# Adafruit_PA1010D_Mini_GPS.net
KiCad netlist of a schematic drawn in EAGLE
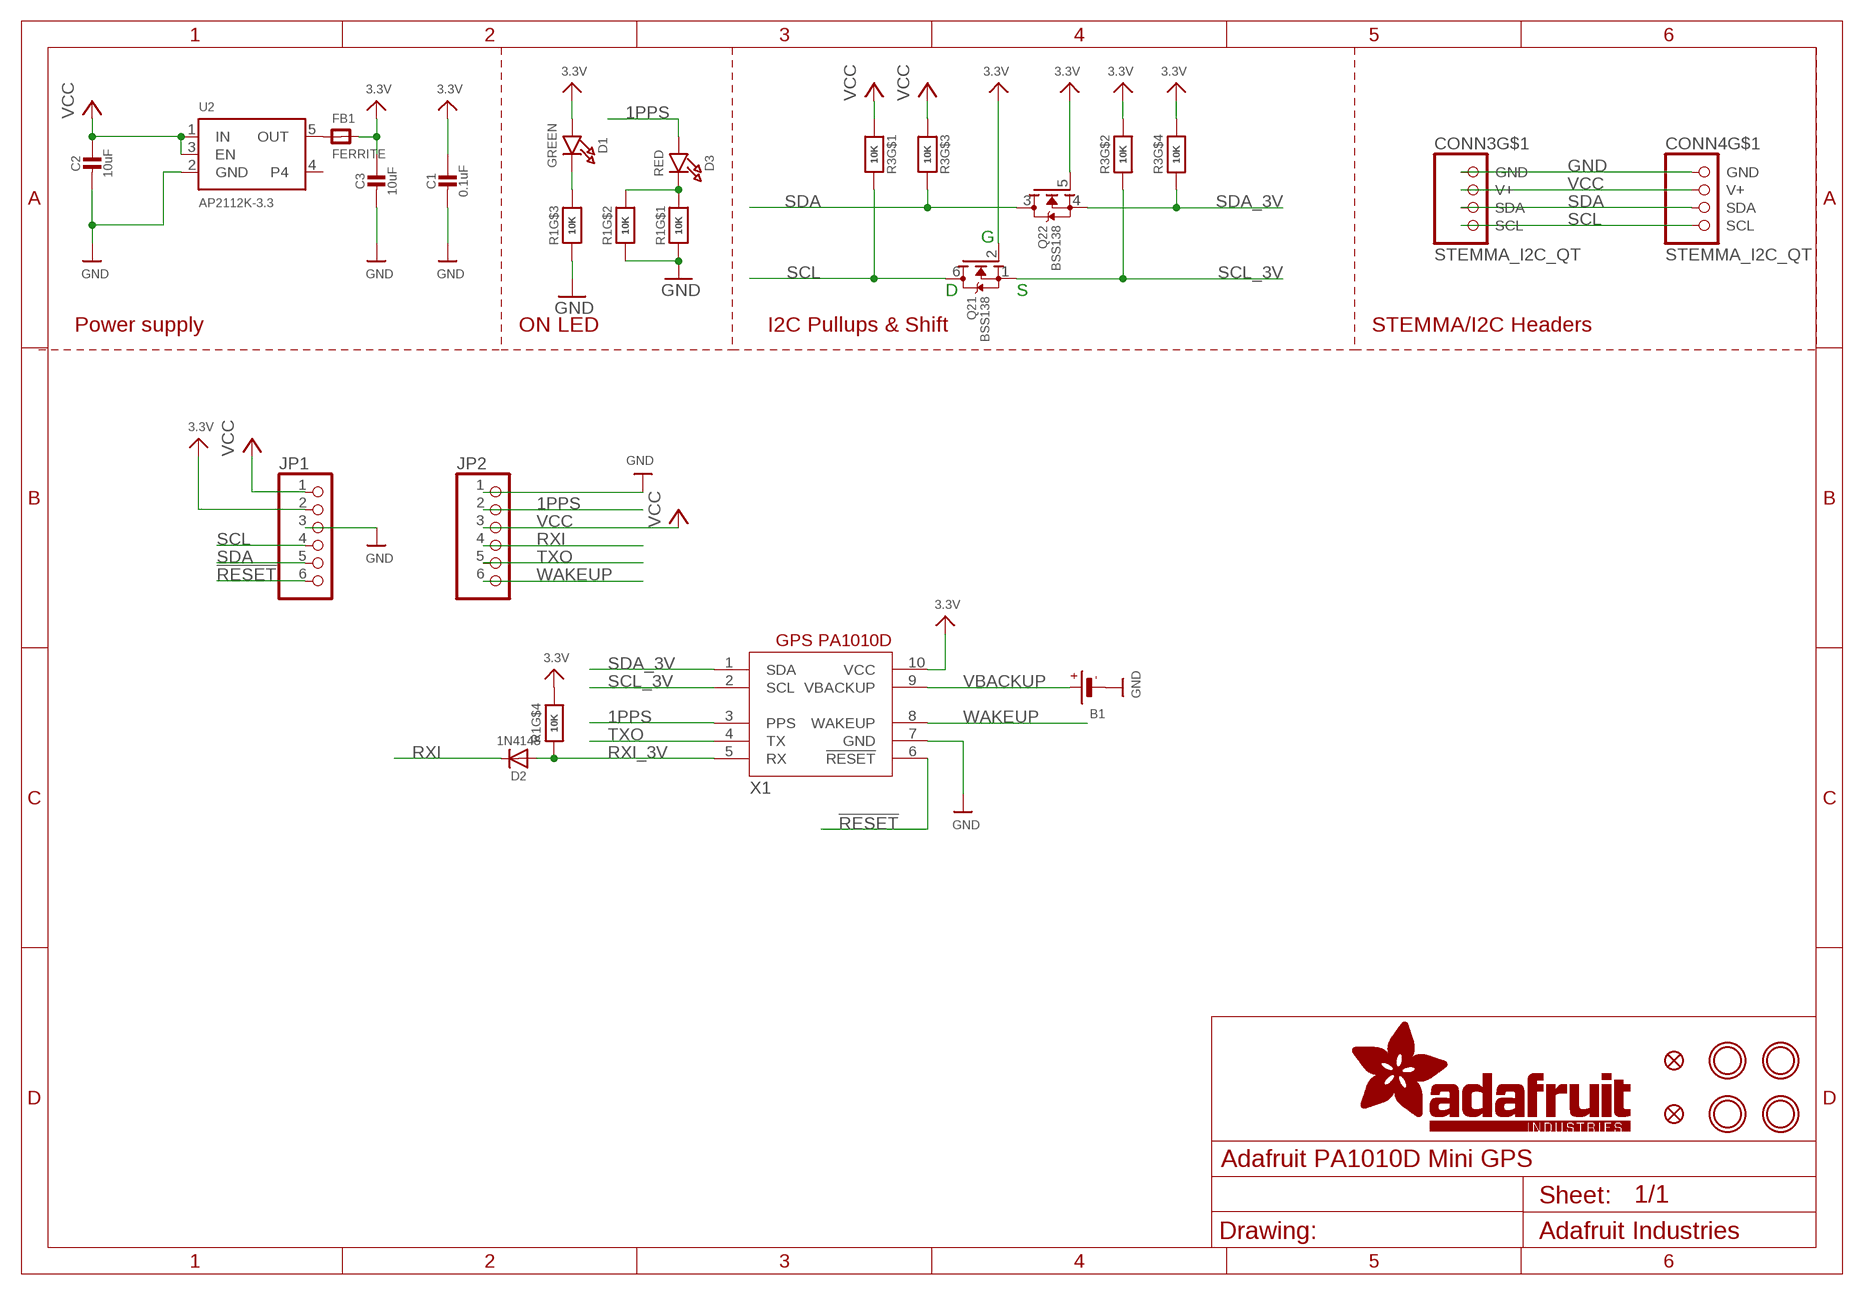
[diagram p0: schematic, sheet 1]

(export (version "E")
  (design (tool "Eeschema 10.0.6"))
  (components
    (comp (ref "B1")
      (value "BATTERYCR1220_2")
      (footprint "eagle-import:CR1220-2")
      (libsource (lib "eagle-import") (part "BATTERYCR1220_2"))
    )
    (comp (ref "C1")
      (value "0.1uF")
      (footprint "eagle-import:0603-NO")
      (libsource (lib "eagle-import") (part "CAP_CERAMIC0603_NO"))
    )
    (comp (ref "C2")
      (value "10uF")
      (footprint "eagle-import:0805-NO")
      (libsource (lib "eagle-import") (part "CAP_CERAMIC0805-NOOUTLINE"))
    )
    (comp (ref "C3")
      (value "10uF")
      (footprint "eagle-import:0805-NO")
      (libsource (lib "eagle-import") (part "CAP_CERAMIC0805-NOOUTLINE"))
    )
    (comp (ref "CONN3")
      (value "STEMMA_I2C_QT")
      (footprint "eagle-import:JST_SH4")
      (libsource (lib "eagle-import") (part "STEMMA_I2C_QT"))
    )
    (comp (ref "CONN4")
      (value "STEMMA_I2C_QT")
      (footprint "eagle-import:JST_SH4")
      (libsource (lib "eagle-import") (part "STEMMA_I2C_QT"))
    )
    (comp (ref "D1")
      (value "GREEN")
      (footprint "eagle-import:CHIPLED_0603_NOOUTLINE")
      (libsource (lib "eagle-import") (part "LED0603_NOOUTLINE"))
    )
    (comp (ref "D2")
      (value "1N4148")
      (footprint "eagle-import:SOD-323")
      (libsource (lib "eagle-import") (part "DIODESOD-323"))
    )
    (comp (ref "D3")
      (value "RED")
      (footprint "eagle-import:CHIPLED_0603_NOOUTLINE")
      (libsource (lib "eagle-import") (part "LED0603_NOOUTLINE"))
    )
    (comp (ref "FB1")
      (value "FERRITE")
      (footprint "eagle-import:0805-NO")
      (libsource (lib "eagle-import") (part "FERRITE-0805NO"))
    )
    (comp (ref "FID3")
      (value "FIDUCIAL_1MM")
      (footprint "eagle-import:FIDUCIAL_1MM")
      (libsource (lib "eagle-import") (part "FIDUCIAL_1MM"))
    )
    (comp (ref "FID4")
      (value "FIDUCIAL_1MM")
      (footprint "eagle-import:FIDUCIAL_1MM")
      (libsource (lib "eagle-import") (part "FIDUCIAL_1MM"))
    )
    (comp (ref "JP1")
      (value "HEADER-1X670MIL")
      (footprint "eagle-import:1X06_ROUND_70")
      (libsource (lib "eagle-import") (part "HEADER-1X670MIL"))
    )
    (comp (ref "JP2")
      (value "HEADER-1X670MIL")
      (footprint "eagle-import:1X06_ROUND_70")
      (libsource (lib "eagle-import") (part "HEADER-1X670MIL"))
    )
    (comp (ref "Q2")
      (value "BSS138")
      (footprint "eagle-import:SOT363")
      (libsource (lib "eagle-import") (part "MOSFET-N_DUAL"))
    )
    (comp (ref "R1")
      (value "10K")
      (footprint "eagle-import:RESPACK_4X0603")
      (libsource (lib "eagle-import") (part "RESISTOR_4PACK"))
    )
    (comp (ref "R3")
      (value "10K")
      (footprint "eagle-import:RESPACK_4X0603")
      (libsource (lib "eagle-import") (part "RESISTOR_4PACK"))
    )
    (comp (ref "U$1")
      (value "MOUNTINGHOLE2.5")
      (footprint "eagle-import:MOUNTINGHOLE_2.5_PLATED")
      (libsource (lib "eagle-import") (part "MOUNTINGHOLE2.5"))
    )
    (comp (ref "U$17")
      (value "MOUNTINGHOLE2.5")
      (footprint "eagle-import:MOUNTINGHOLE_2.5_PLATED")
      (libsource (lib "eagle-import") (part "MOUNTINGHOLE2.5"))
    )
    (comp (ref "U$19")
      (value "MOUNTINGHOLE2.5")
      (footprint "eagle-import:MOUNTINGHOLE_2.5_PLATED")
      (libsource (lib "eagle-import") (part "MOUNTINGHOLE2.5"))
    )
    (comp (ref "U$21")
      (value "MOUNTINGHOLE2.5")
      (footprint "eagle-import:MOUNTINGHOLE_2.5_PLATED")
      (libsource (lib "eagle-import") (part "MOUNTINGHOLE2.5"))
    )
    (comp (ref "U2")
      (value "AP2112K-3.3")
      (footprint "eagle-import:SOT23-5")
      (libsource (lib "eagle-import") (part "VREG_SOT23-5"))
    )
    (comp (ref "X1")
      (value "GPS_PA1010D")
      (footprint "eagle-import:GPS_PA1010D")
      (libsource (lib "eagle-import") (part "GPS_PA1010D"))
    )
  )
  (nets
    (net (code "1") (name "/1PPS") (class "Default")
      (node (ref "D3") (pin "A") (pinfunction "A_A") (pintype "passive"))
      (node (ref "JP2") (pin "2") (pinfunction "2_2") (pintype "passive"))
      (node (ref "X1") (pin "3") (pinfunction "PPS_3") (pintype "output"))
    )
    (net (code "2") (name "/RXI") (class "Default")
      (node (ref "D2") (pin "C") (pinfunction "C_C") (pintype "passive"))
      (node (ref "JP2") (pin "4") (pinfunction "4_4") (pintype "passive"))
    )
    (net (code "3") (name "/RXI_3V") (class "Default")
      (node (ref "D2") (pin "A") (pinfunction "A_A") (pintype "passive"))
      (node (ref "R1") (pin "5") (pinfunction "2_5") (pintype "passive"))
      (node (ref "X1") (pin "5") (pinfunction "RX_5") (pintype "input"))
    )
    (net (code "4") (name "/SCL") (class "Default")
      (node (ref "CONN3") (pin "4") (pinfunction "SCL_4") (pintype "passive"))
      (node (ref "CONN4") (pin "4") (pinfunction "SCL_4") (pintype "passive"))
      (node (ref "JP1") (pin "4") (pinfunction "4_4") (pintype "passive"))
      (node (ref "Q2") (pin "6") (pinfunction "D_6") (pintype "bidirectional"))
      (node (ref "R3") (pin "8") (pinfunction "2_8") (pintype "passive"))
    )
    (net (code "5") (name "/SCL_3V") (class "Default")
      (node (ref "Q2") (pin "1") (pinfunction "S_1") (pintype "bidirectional"))
      (node (ref "R3") (pin "7") (pinfunction "2_7") (pintype "passive"))
      (node (ref "X1") (pin "2") (pinfunction "SCL_2") (pintype "bidirectional"))
    )
    (net (code "6") (name "/SDA") (class "Default")
      (node (ref "CONN3") (pin "3") (pinfunction "SDA_3") (pintype "passive"))
      (node (ref "CONN4") (pin "3") (pinfunction "SDA_3") (pintype "passive"))
      (node (ref "JP1") (pin "5") (pinfunction "5_5") (pintype "passive"))
      (node (ref "Q2") (pin "3") (pinfunction "D_3") (pintype "bidirectional"))
      (node (ref "R3") (pin "6") (pinfunction "2_6") (pintype "passive"))
    )
    (net (code "7") (name "/SDA_3V") (class "Default")
      (node (ref "Q2") (pin "4") (pinfunction "S_4") (pintype "bidirectional"))
      (node (ref "R3") (pin "5") (pinfunction "2_5") (pintype "passive"))
      (node (ref "X1") (pin "1") (pinfunction "SDA_1") (pintype "bidirectional"))
    )
    (net (code "8") (name "/TXO") (class "Default")
      (node (ref "JP2") (pin "5") (pinfunction "5_5") (pintype "passive"))
      (node (ref "X1") (pin "4") (pinfunction "TX_4") (pintype "output"))
    )
    (net (code "9") (name "/VBACKUP") (class "Default")
      (node (ref "B1") (pin "+") (pinfunction "+_+") (pintype "passive"))
      (node (ref "X1") (pin "9") (pinfunction "VBACKUP_9") (pintype "power_in"))
    )
    (net (code "10") (name "/WAKEUP") (class "Default")
      (node (ref "JP2") (pin "6") (pinfunction "6_6") (pintype "passive"))
      (node (ref "X1") (pin "8") (pinfunction "WAKEUP_8") (pintype "input"))
    )
    (net (code "11") (name "/~{RESET}") (class "Default")
      (node (ref "JP1") (pin "6") (pinfunction "6_6") (pintype "passive"))
      (node (ref "X1") (pin "6") (pinfunction "~{RESET}_6") (pintype "input"))
    )
    (net (code "12") (name "3.3V") (class "Default")
      (node (ref "C1") (pin "1") (pinfunction "1_1") (pintype "passive"))
      (node (ref "C3") (pin "1") (pinfunction "1_1") (pintype "passive"))
      (node (ref "D1") (pin "A") (pinfunction "A_A") (pintype "passive"))
      (node (ref "FB1") (pin "2") (pinfunction "P$2_2") (pintype "passive"))
      (node (ref "JP1") (pin "2") (pinfunction "2_2") (pintype "passive"))
      (node (ref "Q2") (pin "2") (pinfunction "G_2") (pintype "bidirectional"))
      (node (ref "Q2") (pin "5") (pinfunction "G_5") (pintype "bidirectional"))
      (node (ref "R1") (pin "4") (pinfunction "1_4") (pintype "passive"))
      (node (ref "R3") (pin "2") (pinfunction "1_2") (pintype "passive"))
      (node (ref "R3") (pin "4") (pinfunction "1_4") (pintype "passive"))
      (node (ref "X1") (pin "10") (pinfunction "VCC_10") (pintype "power_in"))
    )
    (net (code "13") (name "GND") (class "Default")
      (node (ref "B1") (pin "-") (pinfunction "-_-") (pintype "passive"))
      (node (ref "C1") (pin "2") (pinfunction "2_2") (pintype "passive"))
      (node (ref "C2") (pin "2") (pinfunction "2_2") (pintype "passive"))
      (node (ref "C3") (pin "2") (pinfunction "2_2") (pintype "passive"))
      (node (ref "CONN3") (pin "1") (pinfunction "GND_1") (pintype "passive"))
      (node (ref "CONN4") (pin "1") (pinfunction "GND_1") (pintype "passive"))
      (node (ref "JP1") (pin "3") (pinfunction "3_3") (pintype "passive"))
      (node (ref "JP2") (pin "1") (pinfunction "1_1") (pintype "passive"))
      (node (ref "R1") (pin "1") (pinfunction "1_1") (pintype "passive"))
      (node (ref "R1") (pin "2") (pinfunction "1_2") (pintype "passive"))
      (node (ref "R1") (pin "3") (pinfunction "1_3") (pintype "passive"))
      (node (ref "U2") (pin "2") (pinfunction "GND_2") (pintype "power_in"))
      (node (ref "X1") (pin "7") (pinfunction "GND_7") (pintype "power_in"))
    )
    (net (code "14") (name "Net-(FB1-P$1)") (class "Default")
      (node (ref "FB1") (pin "1") (pinfunction "P$1_1") (pintype "passive"))
      (node (ref "U2") (pin "5") (pinfunction "OUT_5") (pintype "power_in"))
    )
    (net (code "15") (name "Net-(R1A-2)") (class "Default")
      (node (ref "D3") (pin "C") (pinfunction "C_C") (pintype "passive"))
      (node (ref "R1") (pin "7") (pinfunction "2_7") (pintype "passive"))
      (node (ref "R1") (pin "8") (pinfunction "2_8") (pintype "passive"))
    )
    (net (code "16") (name "Net-(R1C-2)") (class "Default")
      (node (ref "D1") (pin "C") (pinfunction "C_C") (pintype "passive"))
      (node (ref "R1") (pin "6") (pinfunction "2_6") (pintype "passive"))
    )
    (net (code "17") (name "VCC") (class "Default")
      (node (ref "C2") (pin "1") (pinfunction "1_1") (pintype "passive"))
      (node (ref "CONN3") (pin "2") (pinfunction "V+_2") (pintype "passive"))
      (node (ref "CONN4") (pin "2") (pinfunction "V+_2") (pintype "passive"))
      (node (ref "JP1") (pin "1") (pinfunction "1_1") (pintype "passive"))
      (node (ref "JP2") (pin "3") (pinfunction "3_3") (pintype "passive"))
      (node (ref "R3") (pin "1") (pinfunction "1_1") (pintype "passive"))
      (node (ref "R3") (pin "3") (pinfunction "1_3") (pintype "passive"))
      (node (ref "U2") (pin "1") (pinfunction "IN_1") (pintype "power_in"))
      (node (ref "U2") (pin "3") (pinfunction "EN_3") (pintype "input"))
    )
    (net (code "18") (name "unconnected-(U2-P4-Pad4)") (class "Default")
      (node (ref "U2") (pin "4") (pinfunction "P4_4") (pintype "bidirectional"))
    )
  )
)
